# CC2530.net
KiCad netlist of a schematic drawn in Altium Designer
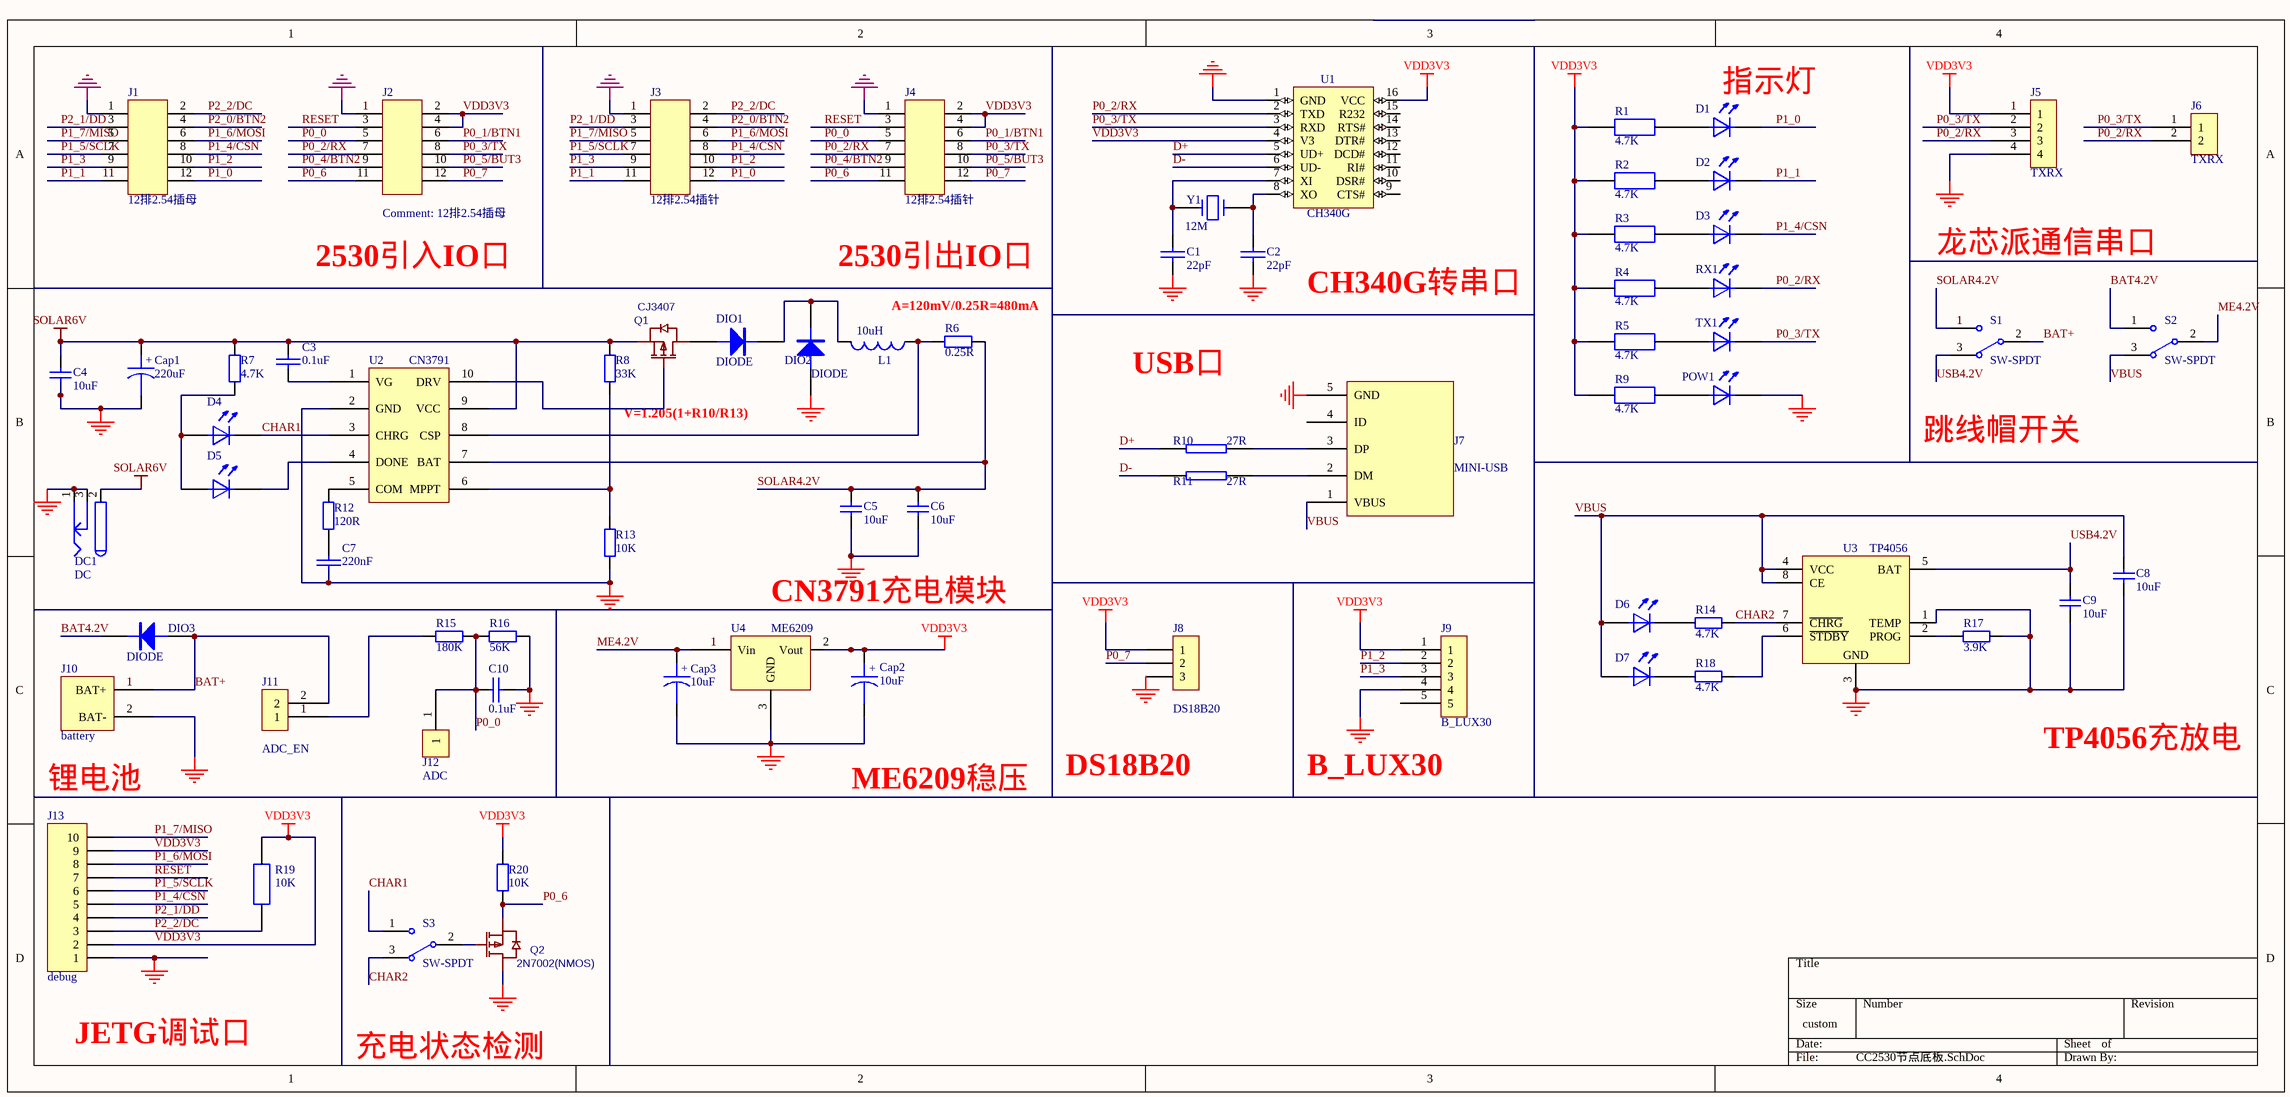
[diagram p0: CC2530节点底板.SchDoc]

(export (version "E")
  (design (tool "Eeschema 10.0.6"))
  (components
    (comp (ref "C1")
      (value "22pF")
      (footprint "C 0603_L")
      (description "Capacitor")
      (libsource (lib "*") (part "CAP"))
    )
    (comp (ref "C2")
      (value "22pF")
      (footprint "C 0603_L")
      (description "Capacitor")
      (libsource (lib "*") (part "CAP"))
    )
    (comp (ref "C3")
      (value "0.1uF")
      (footprint "C 0603_L")
      (description "Capacitor")
      (libsource (lib "*") (part "CAP"))
    )
    (comp (ref "C4")
      (value "10uF")
      (footprint "C 0805_L")
      (description "无极性电容")
      (fields (field (name "PUBLISHER") "Altium Limited"))
      (libsource (lib "Fszhang") (part "Cap"))
    )
    (comp (ref "C5")
      (value "10uF")
      (footprint "C 0805_L")
      (description "无极性电容")
      (fields (field (name "PUBLISHER") "Altium Limited"))
      (libsource (lib "Fszhang") (part "Cap"))
    )
    (comp (ref "C6")
      (value "10uF")
      (footprint "C 0805_L")
      (description "无极性电容")
      (fields (field (name "PUBLISHER") "Altium Limited"))
      (libsource (lib "Fszhang") (part "Cap"))
    )
    (comp (ref "C7")
      (value "220nF")
      (footprint "C 0603_L")
      (description "Capacitor")
      (libsource (lib "*") (part "CAP"))
    )
    (comp (ref "C8")
      (value "10uF")
      (footprint "C 0805_L")
      (description "无极性电容")
      (fields (field (name "PUBLISHER") "Altium Limited"))
      (libsource (lib "Fszhang") (part "Cap"))
    )
    (comp (ref "C9")
      (value "10uF")
      (footprint "C 0805_L")
      (description "无极性电容")
      (fields (field (name "PUBLISHER") "Altium Limited"))
      (libsource (lib "Fszhang") (part "Cap"))
    )
    (comp (ref "C10")
      (value "0.1uF")
      (footprint "C 0603_L")
      (description "Capacitor")
      (libsource (lib "*") (part "CAP"))
    )
    (comp (ref "Cap1")
      (value "220uF")
      (footprint "CM E(8*10.2)")
      (description "Capacitor")
      (libsource (lib "*") (part "CAPACITOR POL"))
    )
    (comp (ref "Cap2")
      (value "10uF")
      (footprint "CM C(5*5.4)")
      (description "Capacitor")
      (libsource (lib "*") (part "CAPACITOR POL"))
    )
    (comp (ref "Cap3")
      (value "10uF")
      (footprint "CM C(5*5.4)")
      (description "Capacitor")
      (libsource (lib "*") (part "CAPACITOR POL"))
    )
    (comp (ref "D1") (value "~") (footprint "LED 0805W") (libsource (lib "*") (part "LED")))
    (comp (ref "D2") (value "~") (footprint "LED 0805W") (libsource (lib "*") (part "LED")))
    (comp (ref "D3") (value "~") (footprint "LED 0805W") (libsource (lib "*") (part "LED")))
    (comp (ref "D4") (value "~") (footprint "LED 0805R") (libsource (lib "*") (part "LED")))
    (comp (ref "D5") (value "~") (footprint "LED 0805G") (libsource (lib "*") (part "LED")))
    (comp (ref "D6") (value "~") (footprint "LED 0805R") (libsource (lib "*") (part "LED")))
    (comp (ref "D7") (value "~") (footprint "LED 0805G") (libsource (lib "*") (part "LED")))
    (comp (ref "DC1")
      (value "DC")
      (footprint "DC-005")
      (description "Low Voltage Power Supply Connector")
      (fields (field (name "PUBLISHER") "*"))
      (libsource (lib "*") (part "PWR2.5"))
    )
    (comp (ref "DIO1")
      (value "DIODE")
      (footprint "SOD-323")
      (description "1N5817")
      (libsource (lib "*") (part "DIODE"))
    )
    (comp (ref "DIO2")
      (value "DIODE")
      (footprint "SOD-323")
      (description "1N5817")
      (libsource (lib "*") (part "DIODE"))
    )
    (comp (ref "DIO3")
      (value "DIODE")
      (footprint "SOD-323")
      (description "1N5817")
      (libsource (lib "*") (part "DIODE"))
    )
    (comp (ref "J1") (value "12排2.54插母") (footprint "HDR2.54-M-LS-2x6P") (libsource (lib "*") (part "CON12")))
    (comp (ref "J2") (value "12排2.54插母") (footprint "HDR2.54-M-LS-2x6P") (libsource (lib "*") (part "CON12")))
    (comp (ref "J3") (value "12排2.54插针") (footprint "HDR2.54-LI-2x6P") (libsource (lib "*") (part "CON12")))
    (comp (ref "J4") (value "12排2.54插针") (footprint "HDR2.54-LI-2x6P") (libsource (lib "*") (part "CON12")))
    (comp (ref "J5")
      (value "TXRX")
      (footprint "HDR2.54-M-LI-4P")
      (libsource (lib "串口收发") (part "Component_1"))
    )
    (comp (ref "J6") (value "TXRX") (footprint "HDR2.54-LI-2P") (libsource (lib "") (part "Component_1_1")))
    (comp (ref "J7")
      (value "MINI-USB")
      (footprint "USB-MINI-A")
      (libsource (lib "MINI-USB") (part "Component_1"))
    )
    (comp (ref "J8")
      (value "~")
      (footprint "HDR2.54-M-LI-3P")
      (description "Connector")
      (libsource (lib "*") (part "CON3"))
    )
    (comp (ref "J9")
      (value "B_LUX30")
      (footprint "HDR2.0-M-LI-5P")
      (libsource (lib "B_LUX30") (part "Component_1"))
    )
    (comp (ref "J10") (value "battery") (footprint "单节贴片锂电池座") (libsource (lib "BAT") (part "Component_1")))
    (comp (ref "J11")
      (value "ADC_EN")
      (footprint "HDR2.54-LI-2P")
      (libsource (lib "") (part "Component_1_2"))
    )
    (comp (ref "J12")
      (value "ADC")
      (footprint "HDR2.54-LI-1P")
      (libsource (lib "ADC采样") (part "Component_1"))
    )
    (comp (ref "J13")
      (value "debug")
      (footprint "DC-2.54-L-Z-10P")
      (description "Connector")
      (libsource (lib "*") (part "CON10"))
    )
    (comp (ref "L1")
      (value "10uH")
      (footprint "NR5020")
      (description "NR5020")
      (libsource (lib "*") (part "L"))
    )
    (comp (ref "POW1") (value "~") (footprint "LED 0805R") (libsource (lib "*") (part "LED")))
    (comp (ref "Q1")
      (value "CJ3407")
      (footprint "SOT-23")
      (fields
        (field (name "BOM_MANUFACTURER PART") "AOD413A")
        (field (name "BOM_SUPPLIER PART") "C115837")
        (field (name "CONTRIBUTOR") "LCSC")
      )
      (libsource (lib "altium-import") (part "root_1_AOD413A_"))
    )
    (comp (ref "Q2")
      (value "2N7002(NMOS)")
      (footprint "SOT-23")
      (description "2N7002")
      (fields
        (field (name "BOM_MANUFACTURER PART") "AOD413A")
        (field (name "BOM_SUPPLIER PART") "C115837")
        (field (name "CONTRIBUTOR") "LCSC")
      )
      (libsource (lib "altium-import") (part "root_0_AOD413A_"))
    )
    (comp (ref "R1") (value "4.7K") (footprint "R 0603-HP_L") (libsource (lib "*") (part "R")))
    (comp (ref "R2") (value "4.7K") (footprint "R 0603-HP_L") (libsource (lib "*") (part "R")))
    (comp (ref "R3") (value "4.7K") (footprint "R 0603-HP_L") (libsource (lib "*") (part "R")))
    (comp (ref "R4") (value "4.7K") (footprint "R 0603-HP_L") (libsource (lib "*") (part "R")))
    (comp (ref "R5") (value "4.7K") (footprint "R 0603-HP_L") (libsource (lib "*") (part "R")))
    (comp (ref "R6")
      (value "0.25R")
      (footprint "R 0805-HP_L")
      (description "贴片电阻")
      (fields (field (name "PUBLISHER") "Altium Limited"))
      (libsource (lib "Fszhang") (part "Res1"))
    )
    (comp (ref "R7")
      (value "4.7K")
      (footprint "R 0603-HP_L")
      (description "贴片电阻")
      (fields (field (name "PUBLISHER") "Altium Limited"))
      (libsource (lib "") (part "Res1_1"))
    )
    (comp (ref "R8")
      (value "33K")
      (footprint "R 0603-HP_L")
      (description "贴片电阻")
      (fields (field (name "Comment") "75K") (field (name "PUBLISHER") "Altium Limited"))
      (libsource (lib "") (part "Res1_1"))
    )
    (comp (ref "R9") (value "4.7K") (footprint "R 0603-HP_L") (libsource (lib "*") (part "R")))
    (comp (ref "R10") (value "27R") (footprint "R 0603-HP_L") (libsource (lib "*") (part "RES2")))
    (comp (ref "R11") (value "27R") (footprint "R 0603-HP_L") (libsource (lib "*") (part "RES2")))
    (comp (ref "R12")
      (value "120R")
      (footprint "R 0603-HP_L")
      (description "贴片电阻")
      (fields (field (name "PUBLISHER") "Altium Limited"))
      (libsource (lib "") (part "Res1_1"))
    )
    (comp (ref "R13")
      (value "10K")
      (footprint "R 0603-HP_L")
      (description "贴片电阻")
      (fields (field (name "PUBLISHER") "Altium Limited"))
      (libsource (lib "") (part "Res1_1"))
    )
    (comp (ref "R14")
      (value "4.7K")
      (footprint "R 0603-HP_L")
      (description "贴片电阻")
      (fields (field (name "Comment") "1K") (field (name "PUBLISHER") "Altium Limited"))
      (libsource (lib "Fszhang") (part "Res1"))
    )
    (comp (ref "R15")
      (value "180K")
      (footprint "R 0603-HP_L")
      (description "贴片电阻")
      (fields (field (name "Comment") "168K") (field (name "PUBLISHER") "Altium Limited"))
      (libsource (lib "Fszhang") (part "Res1"))
    )
    (comp (ref "R16")
      (value "56K")
      (footprint "R 0603-HP_L")
      (description "贴片电阻")
      (fields (field (name "PUBLISHER") "Altium Limited"))
      (libsource (lib "Fszhang") (part "Res1"))
    )
    (comp (ref "R17")
      (value "3.9K")
      (footprint "R 0603-HP_L")
      (description "贴片电阻")
      (fields (field (name "PUBLISHER") "Altium Limited"))
      (libsource (lib "Fszhang") (part "Res1"))
    )
    (comp (ref "R18")
      (value "4.7K")
      (footprint "R 0603-HP_L")
      (description "贴片电阻")
      (fields (field (name "Comment") "1K") (field (name "PUBLISHER") "Altium Limited"))
      (libsource (lib "Fszhang") (part "Res1"))
    )
    (comp (ref "R19") (value "10K") (footprint "R 0603-HP_L") (libsource (lib "*") (part "R")))
    (comp (ref "R20")
      (value "10K")
      (footprint "R 0603-HP_L")
      (description "贴片电阻")
      (fields (field (name "Comment") "168K") (field (name "PUBLISHER") "Altium Limited"))
      (libsource (lib "") (part "Res1_1"))
    )
    (comp (ref "RX1") (value "~") (footprint "LED 0805R") (libsource (lib "*") (part "LED")))
    (comp (ref "S1")
      (value "SW-SPDT")
      (footprint "HDR2.54-LI-3P")
      (description "开关")
      (fields (field (name "PUBLISHER") "Altium Limited"))
      (libsource (lib "Fszhang") (part "SW-SPDT"))
    )
    (comp (ref "S2")
      (value "SW-SPDT")
      (footprint "HDR2.54-LI-3P")
      (description "开关")
      (fields (field (name "PUBLISHER") "Altium Limited"))
      (libsource (lib "Fszhang") (part "SW-SPDT"))
    )
    (comp (ref "S3")
      (value "SW-SPDT")
      (footprint "HDR2.54-LI-3P")
      (description "开关")
      (fields (field (name "PUBLISHER") "Altium Limited"))
      (libsource (lib "Fszhang") (part "SW-SPDT"))
    )
    (comp (ref "TX1") (value "~") (footprint "LED 0805R") (libsource (lib "*") (part "LED")))
    (comp (ref "U1")
      (value "CH340G")
      (footprint "SOP16")
      (description "CH340")
      (libsource (lib "*") (part "CH340G"))
    )
    (comp (ref "U2")
      (value "CN3791")
      (footprint "SSOP-10_150mil")
      (libsource (lib "CN3791") (part "Component_1"))
    )
    (comp (ref "U3")
      (value "TP4056")
      (footprint "SOP8")
      (description "锂电池充电管理")
      (libsource (lib "Fszhang") (part "TP4056"))
    )
    (comp (ref "U4") (value "ME6209") (footprint "SOT89_M") (libsource (lib "ME6209") (part "Component_1")))
    (comp (ref "Y1")
      (value "12M")
      (footprint "OSC HC-49S")
      (description "32K")
      (libsource (lib "*") (part "CRYSTAL"))
    )
  )
  (nets
    (net (code "1") (name "/BAT+") (class "Default")
      (node (ref "DIO3") (pin "1") (pinfunction "A_1") (pintype "passive"))
      (node (ref "J10") (pin "1") (pinfunction "BAT+_1") (pintype "passive"))
      (node (ref "J11") (pin "2") (pinfunction "2_2") (pintype "passive"))
      (node (ref "S1") (pin "2") (pinfunction "2_2") (pintype "passive"))
    )
    (net (code "2") (name "/BAT4.2V") (class "Default")
      (node (ref "DIO3") (pin "2") (pinfunction "K_2") (pintype "passive"))
      (node (ref "S2") (pin "1") (pinfunction "1_1") (pintype "passive"))
    )
    (net (code "3") (name "/CHAR1") (class "Default")
      (node (ref "D4") (pin "2") (pinfunction "2_2") (pintype "passive"))
      (node (ref "S3") (pin "1") (pinfunction "1_1") (pintype "passive"))
      (node (ref "U2") (pin "3") (pinfunction "CHRG_3") (pintype "passive"))
    )
    (net (code "4") (name "/CHAR2") (class "Default")
      (node (ref "R14") (pin "1") (pinfunction "1_1") (pintype "passive"))
      (node (ref "S3") (pin "3") (pinfunction "3_3") (pintype "passive"))
      (node (ref "U3") (pin "7") (pinfunction "~{CHRG}_7") (pintype "passive"))
    )
    (net (code "5") (name "/D+") (class "Default")
      (node (ref "R10") (pin "1") (pinfunction "1_1") (pintype "passive"))
      (node (ref "U1") (pin "5") (pinfunction "UD+_5") (pintype "bidirectional"))
    )
    (net (code "6") (name "/D-") (class "Default")
      (node (ref "R11") (pin "1") (pinfunction "1_1") (pintype "passive"))
      (node (ref "U1") (pin "6") (pinfunction "UD-_6") (pintype "bidirectional"))
    )
    (net (code "7") (name "/ME4.2V") (class "Default")
      (node (ref "Cap3") (pin "1") (pinfunction "1_1") (pintype "passive"))
      (node (ref "S2") (pin "2") (pinfunction "2_2") (pintype "passive"))
      (node (ref "U4") (pin "1") (pinfunction "Vin_1") (pintype "passive"))
    )
    (net (code "8") (name "/P0_0") (class "Default")
      (node (ref "C10") (pin "2") (pinfunction "2_2") (pintype "passive"))
      (node (ref "J12") (pin "1") (pinfunction "1_1") (pintype "passive"))
      (node (ref "J2") (pin "5") (pinfunction "5_5") (pintype "passive"))
      (node (ref "J4") (pin "5") (pinfunction "5_5") (pintype "passive"))
      (node (ref "R15") (pin "1") (pinfunction "1_1") (pintype "passive"))
      (node (ref "R16") (pin "2") (pinfunction "2_2") (pintype "passive"))
    )
    (net (code "9") (name "/P0_1{slash}BTN1") (class "Default")
      (node (ref "J2") (pin "6") (pinfunction "6_6") (pintype "passive"))
      (node (ref "J4") (pin "6") (pinfunction "6_6") (pintype "passive"))
    )
    (net (code "10") (name "/P0_2{slash}RX") (class "Default")
      (node (ref "J2") (pin "7") (pinfunction "7_7") (pintype "passive"))
      (node (ref "J4") (pin "7") (pinfunction "7_7") (pintype "passive"))
      (node (ref "J5") (pin "3") (pinfunction "3_3") (pintype "passive"))
      (node (ref "J6") (pin "2") (pinfunction "2_2") (pintype "passive"))
      (node (ref "RX1") (pin "2") (pinfunction "2_2") (pintype "passive"))
      (node (ref "U1") (pin "2") (pinfunction "TXD_2") (pintype "bidirectional"))
    )
    (net (code "11") (name "/P0_3{slash}TX") (class "Default")
      (node (ref "J2") (pin "8") (pinfunction "8_8") (pintype "passive"))
      (node (ref "J4") (pin "8") (pinfunction "8_8") (pintype "passive"))
      (node (ref "J5") (pin "2") (pinfunction "2_2") (pintype "passive"))
      (node (ref "J6") (pin "1") (pinfunction "1_1") (pintype "passive"))
      (node (ref "TX1") (pin "2") (pinfunction "2_2") (pintype "passive"))
      (node (ref "U1") (pin "3") (pinfunction "RXD_3") (pintype "bidirectional"))
    )
    (net (code "12") (name "/P0_4{slash}BTN2") (class "Default")
      (node (ref "J2") (pin "9") (pinfunction "9_9") (pintype "passive"))
      (node (ref "J4") (pin "9") (pinfunction "9_9") (pintype "passive"))
    )
    (net (code "13") (name "/P0_5{slash}BUT3") (class "Default")
      (node (ref "J2") (pin "10") (pinfunction "10_10") (pintype "passive"))
      (node (ref "J4") (pin "10") (pinfunction "10_10") (pintype "passive"))
    )
    (net (code "14") (name "/P0_6") (class "Default")
      (node (ref "J2") (pin "11") (pinfunction "11_11") (pintype "passive"))
      (node (ref "J4") (pin "11") (pinfunction "11_11") (pintype "passive"))
      (node (ref "Q2") (pin "3") (pinfunction "S_3") (pintype "passive"))
      (node (ref "R20") (pin "2") (pinfunction "2_2") (pintype "passive"))
    )
    (net (code "15") (name "/P0_7") (class "Default")
      (node (ref "J2") (pin "12") (pinfunction "12_12") (pintype "passive"))
      (node (ref "J4") (pin "12") (pinfunction "12_12") (pintype "passive"))
      (node (ref "J8") (pin "2") (pinfunction "2_2") (pintype "passive"))
    )
    (net (code "16") (name "/P1_0") (class "Default")
      (node (ref "D1") (pin "2") (pinfunction "2_2") (pintype "passive"))
      (node (ref "J1") (pin "12") (pinfunction "12_12") (pintype "passive"))
      (node (ref "J3") (pin "12") (pinfunction "12_12") (pintype "passive"))
    )
    (net (code "17") (name "/P1_1") (class "Default")
      (node (ref "D2") (pin "2") (pinfunction "2_2") (pintype "passive"))
      (node (ref "J1") (pin "11") (pinfunction "11_11") (pintype "passive"))
      (node (ref "J3") (pin "11") (pinfunction "11_11") (pintype "passive"))
    )
    (net (code "18") (name "/P1_2") (class "Default")
      (node (ref "J1") (pin "10") (pinfunction "10_10") (pintype "passive"))
      (node (ref "J3") (pin "10") (pinfunction "10_10") (pintype "passive"))
      (node (ref "J9") (pin "2") (pinfunction "2_2") (pintype "passive"))
    )
    (net (code "19") (name "/P1_3") (class "Default")
      (node (ref "J1") (pin "9") (pinfunction "9_9") (pintype "passive"))
      (node (ref "J3") (pin "9") (pinfunction "9_9") (pintype "passive"))
      (node (ref "J9") (pin "3") (pinfunction "3_3") (pintype "passive"))
    )
    (net (code "20") (name "/P1_4{slash}CSN") (class "Default")
      (node (ref "D3") (pin "2") (pinfunction "2_2") (pintype "passive"))
      (node (ref "J1") (pin "8") (pinfunction "8_8") (pintype "passive"))
      (node (ref "J13") (pin "5") (pinfunction "5_5") (pintype "passive"))
      (node (ref "J3") (pin "8") (pinfunction "8_8") (pintype "passive"))
    )
    (net (code "21") (name "/P1_5{slash}SCLK") (class "Default")
      (node (ref "J1") (pin "7") (pinfunction "7_7") (pintype "passive"))
      (node (ref "J13") (pin "6") (pinfunction "6_6") (pintype "passive"))
      (node (ref "J3") (pin "7") (pinfunction "7_7") (pintype "passive"))
    )
    (net (code "22") (name "/P1_6{slash}MOSI") (class "Default")
      (node (ref "J1") (pin "6") (pinfunction "6_6") (pintype "passive"))
      (node (ref "J13") (pin "8") (pinfunction "8_8") (pintype "passive"))
      (node (ref "J3") (pin "6") (pinfunction "6_6") (pintype "passive"))
    )
    (net (code "23") (name "/P1_7{slash}MISO") (class "Default")
      (node (ref "J1") (pin "5") (pinfunction "5_5") (pintype "passive"))
      (node (ref "J13") (pin "10") (pinfunction "10_10") (pintype "passive"))
      (node (ref "J3") (pin "5") (pinfunction "5_5") (pintype "passive"))
    )
    (net (code "24") (name "/P2_0{slash}BTN2") (class "Default")
      (node (ref "J1") (pin "4") (pinfunction "4_4") (pintype "passive"))
      (node (ref "J3") (pin "4") (pinfunction "4_4") (pintype "passive"))
    )
    (net (code "25") (name "/P2_1{slash}DD") (class "Default")
      (node (ref "J1") (pin "3") (pinfunction "3_3") (pintype "passive"))
      (node (ref "J13") (pin "4") (pinfunction "4_4") (pintype "passive"))
      (node (ref "J3") (pin "3") (pinfunction "3_3") (pintype "passive"))
    )
    (net (code "26") (name "/P2_2{slash}DC") (class "Default")
      (node (ref "J1") (pin "2") (pinfunction "2_2") (pintype "passive"))
      (node (ref "J13") (pin "3") (pinfunction "3_3") (pintype "passive"))
      (node (ref "J3") (pin "2") (pinfunction "2_2") (pintype "passive"))
      (node (ref "R19") (pin "1") (pinfunction "1_1") (pintype "passive"))
    )
    (net (code "27") (name "/RESET") (class "Default")
      (node (ref "J13") (pin "7") (pinfunction "7_7") (pintype "passive"))
      (node (ref "J2") (pin "3") (pinfunction "3_3") (pintype "passive"))
      (node (ref "J4") (pin "3") (pinfunction "3_3") (pintype "passive"))
    )
    (net (code "28") (name "/SOLAR4.2V") (class "Default")
      (node (ref "C5") (pin "1") (pinfunction "1_1") (pintype "passive"))
      (node (ref "C6") (pin "1") (pinfunction "1_1") (pintype "passive"))
      (node (ref "R6") (pin "1") (pinfunction "1_1") (pintype "passive"))
      (node (ref "S1") (pin "1") (pinfunction "1_1") (pintype "passive"))
      (node (ref "U2") (pin "7") (pinfunction "BAT_7") (pintype "passive"))
    )
    (net (code "29") (name "/USB4.2V") (class "Default")
      (node (ref "C9") (pin "1") (pinfunction "1_1") (pintype "passive"))
      (node (ref "S1") (pin "3") (pinfunction "3_3") (pintype "passive"))
      (node (ref "U3") (pin "5") (pinfunction "BAT_5") (pintype "passive"))
    )
    (net (code "30") (name "/VBUS") (class "Default")
      (node (ref "C8") (pin "2") (pinfunction "2_2") (pintype "passive"))
      (node (ref "D6") (pin "1") (pinfunction "1_1") (pintype "passive"))
      (node (ref "D7") (pin "1") (pinfunction "1_1") (pintype "passive"))
      (node (ref "J7") (pin "1") (pinfunction "VBUS_1") (pintype "power_in"))
      (node (ref "S2") (pin "3") (pinfunction "3_3") (pintype "passive"))
      (node (ref "U3") (pin "4") (pinfunction "VCC_4") (pintype "passive"))
      (node (ref "U3") (pin "8") (pinfunction "CE_8") (pintype "passive"))
    )
    (net (code "31") (name "GND") (class "Default")
      (node (ref "C1") (pin "2") (pinfunction "2_2") (pintype "passive"))
      (node (ref "C10") (pin "1") (pinfunction "1_1") (pintype "passive"))
      (node (ref "C2") (pin "2") (pinfunction "2_2") (pintype "passive"))
      (node (ref "C4") (pin "2") (pinfunction "2_2") (pintype "passive"))
      (node (ref "C5") (pin "2") (pinfunction "2_2") (pintype "passive"))
      (node (ref "C6") (pin "2") (pinfunction "2_2") (pintype "passive"))
      (node (ref "C7") (pin "2") (pinfunction "2_2") (pintype "passive"))
      (node (ref "C8") (pin "1") (pinfunction "1_1") (pintype "passive"))
      (node (ref "C9") (pin "2") (pinfunction "2_2") (pintype "passive"))
      (node (ref "Cap1") (pin "2") (pinfunction "2_2") (pintype "passive"))
      (node (ref "Cap2") (pin "2") (pinfunction "2_2") (pintype "passive"))
      (node (ref "Cap3") (pin "2") (pinfunction "2_2") (pintype "passive"))
      (node (ref "DC1") (pin "1") (pinfunction "1_1") (pintype "power_in"))
      (node (ref "DC1") (pin "3") (pinfunction "3_3") (pintype "power_in"))
      (node (ref "DIO2") (pin "1") (pinfunction "A_1") (pintype "passive"))
      (node (ref "J1") (pin "1") (pinfunction "1_1") (pintype "passive"))
      (node (ref "J10") (pin "2") (pinfunction "BAT-_2") (pintype "passive"))
      (node (ref "J13") (pin "1") (pinfunction "1_1") (pintype "passive"))
      (node (ref "J2") (pin "1") (pinfunction "1_1") (pintype "passive"))
      (node (ref "J3") (pin "1") (pinfunction "1_1") (pintype "passive"))
      (node (ref "J4") (pin "1") (pinfunction "1_1") (pintype "passive"))
      (node (ref "J5") (pin "4") (pinfunction "4_4") (pintype "passive"))
      (node (ref "J7") (pin "5") (pinfunction "GND_5") (pintype "power_in"))
      (node (ref "J8") (pin "3") (pinfunction "3_3") (pintype "passive"))
      (node (ref "J9") (pin "4") (pinfunction "4_4") (pintype "passive"))
      (node (ref "POW1") (pin "2") (pinfunction "2_2") (pintype "passive"))
      (node (ref "Q2") (pin "2") (pinfunction "D_2") (pintype "passive"))
      (node (ref "R13") (pin "2") (pinfunction "2_2") (pintype "passive"))
      (node (ref "R16") (pin "1") (pinfunction "1_1") (pintype "passive"))
      (node (ref "R17") (pin "1") (pinfunction "1_1") (pintype "passive"))
      (node (ref "U1") (pin "1") (pinfunction "GND_1") (pintype "bidirectional"))
      (node (ref "U2") (pin "2") (pinfunction "GND_2") (pintype "passive"))
      (node (ref "U3") (pin "1") (pinfunction "TEMP_1") (pintype "passive"))
      (node (ref "U3") (pin "3") (pinfunction "GND_3") (pintype "passive"))
      (node (ref "U4") (pin "3") (pinfunction "GND_3") (pintype "passive"))
    )
    (net (code "32") (name "Net-(C7-Pad1)") (class "Default")
      (node (ref "C7") (pin "1") (pinfunction "1_1") (pintype "passive"))
      (node (ref "R12") (pin "2") (pinfunction "2_2") (pintype "passive"))
    )
    (net (code "33") (name "Net-(D1-Pad1)") (class "Default")
      (node (ref "D1") (pin "1") (pinfunction "1_1") (pintype "passive"))
      (node (ref "R1") (pin "2") (pinfunction "2_2") (pintype "passive"))
    )
    (net (code "34") (name "Net-(D2-Pad1)") (class "Default")
      (node (ref "D2") (pin "1") (pinfunction "1_1") (pintype "passive"))
      (node (ref "R2") (pin "2") (pinfunction "2_2") (pintype "passive"))
    )
    (net (code "35") (name "Net-(D3-Pad1)") (class "Default")
      (node (ref "D3") (pin "1") (pinfunction "1_1") (pintype "passive"))
      (node (ref "R3") (pin "2") (pinfunction "2_2") (pintype "passive"))
    )
    (net (code "36") (name "Net-(D4-Pad1)") (class "Default")
      (node (ref "D4") (pin "1") (pinfunction "1_1") (pintype "passive"))
      (node (ref "D5") (pin "1") (pinfunction "1_1") (pintype "passive"))
      (node (ref "R7") (pin "2") (pinfunction "2_2") (pintype "passive"))
    )
    (net (code "37") (name "Net-(D6-Pad2)") (class "Default")
      (node (ref "D6") (pin "2") (pinfunction "2_2") (pintype "passive"))
      (node (ref "R14") (pin "2") (pinfunction "2_2") (pintype "passive"))
    )
    (net (code "38") (name "Net-(D7-Pad2)") (class "Default")
      (node (ref "D7") (pin "2") (pinfunction "2_2") (pintype "passive"))
      (node (ref "R18") (pin "2") (pinfunction "2_2") (pintype "passive"))
    )
    (net (code "39") (name "Net-(DIO1-A)") (class "Default")
      (node (ref "DIO1") (pin "1") (pinfunction "A_1") (pintype "passive"))
      (node (ref "Q1") (pin "2") (pinfunction "D_2") (pintype "passive"))
    )
    (net (code "40") (name "Net-(DIO1-K)") (class "Default")
      (node (ref "DIO1") (pin "2") (pinfunction "K_2") (pintype "passive"))
      (node (ref "DIO2") (pin "2") (pinfunction "K_2") (pintype "passive"))
      (node (ref "L1") (pin "1") (pinfunction "1_1") (pintype "passive"))
    )
    (net (code "41") (name "Net-(J7-DM)") (class "Default")
      (node (ref "J7") (pin "2") (pinfunction "DM_2") (pintype "passive"))
      (node (ref "R11") (pin "2") (pinfunction "2_2") (pintype "passive"))
    )
    (net (code "42") (name "Net-(J7-DP)") (class "Default")
      (node (ref "J7") (pin "3") (pinfunction "DP_3") (pintype "passive"))
      (node (ref "R10") (pin "2") (pinfunction "2_2") (pintype "passive"))
    )
    (net (code "43") (name "Net-(J11-Pad1)") (class "Default")
      (node (ref "J11") (pin "1") (pinfunction "1_1") (pintype "passive"))
      (node (ref "R15") (pin "2") (pinfunction "2_2") (pintype "passive"))
    )
    (net (code "44") (name "Net-(POW1-Pad1)") (class "Default")
      (node (ref "POW1") (pin "1") (pinfunction "1_1") (pintype "passive"))
      (node (ref "R9") (pin "2") (pinfunction "2_2") (pintype "passive"))
    )
    (net (code "45") (name "Net-(Q1-G)") (class "Default")
      (node (ref "Q1") (pin "1") (pinfunction "G_1") (pintype "passive"))
      (node (ref "U2") (pin "10") (pinfunction "DRV_10") (pintype "passive"))
    )
    (net (code "46") (name "Net-(Q2-G)") (class "Default")
      (node (ref "Q2") (pin "1") (pinfunction "G_1") (pintype "passive"))
      (node (ref "S3") (pin "2") (pinfunction "2_2") (pintype "passive"))
    )
    (net (code "47") (name "Net-(R4-Pad2)") (class "Default")
      (node (ref "R4") (pin "2") (pinfunction "2_2") (pintype "passive"))
      (node (ref "RX1") (pin "1") (pinfunction "1_1") (pintype "passive"))
    )
    (net (code "48") (name "Net-(R5-Pad2)") (class "Default")
      (node (ref "R5") (pin "2") (pinfunction "2_2") (pintype "passive"))
      (node (ref "TX1") (pin "1") (pinfunction "1_1") (pintype "passive"))
    )
    (net (code "49") (name "Net-(U1-XI)") (class "Default")
      (node (ref "C1") (pin "1") (pinfunction "1_1") (pintype "passive"))
      (node (ref "U1") (pin "7") (pinfunction "XI_7") (pintype "bidirectional"))
      (node (ref "Y1") (pin "1") (pinfunction "1_1") (pintype "passive"))
    )
    (net (code "50") (name "Net-(U1-XO)") (class "Default")
      (node (ref "C2") (pin "1") (pinfunction "1_1") (pintype "passive"))
      (node (ref "U1") (pin "8") (pinfunction "XO_8") (pintype "bidirectional"))
      (node (ref "Y1") (pin "2") (pinfunction "2_2") (pintype "passive"))
    )
    (net (code "51") (name "Net-(U2-COM)") (class "Default")
      (node (ref "R12") (pin "1") (pinfunction "1_1") (pintype "passive"))
      (node (ref "U2") (pin "5") (pinfunction "COM_5") (pintype "passive"))
    )
    (net (code "52") (name "Net-(U2-CSP)") (class "Default")
      (node (ref "L1") (pin "2") (pinfunction "2_2") (pintype "passive"))
      (node (ref "R6") (pin "2") (pinfunction "2_2") (pintype "passive"))
      (node (ref "U2") (pin "8") (pinfunction "CSP_8") (pintype "passive"))
    )
    (net (code "53") (name "Net-(U2-DONE)") (class "Default")
      (node (ref "D5") (pin "2") (pinfunction "2_2") (pintype "passive"))
      (node (ref "U2") (pin "4") (pinfunction "DONE_4") (pintype "passive"))
    )
    (net (code "54") (name "Net-(U2-MPPT)") (class "Default")
      (node (ref "R13") (pin "1") (pinfunction "1_1") (pintype "passive"))
      (node (ref "R8") (pin "2") (pinfunction "2_2") (pintype "passive"))
      (node (ref "U2") (pin "6") (pinfunction "MPPT_6") (pintype "passive"))
    )
    (net (code "55") (name "Net-(U2-VG)") (class "Default")
      (node (ref "C3") (pin "2") (pinfunction "2_2") (pintype "passive"))
      (node (ref "U2") (pin "1") (pinfunction "VG_1") (pintype "passive"))
    )
    (net (code "56") (name "Net-(U3-PROG)") (class "Default")
      (node (ref "R17") (pin "2") (pinfunction "2_2") (pintype "passive"))
      (node (ref "U3") (pin "2") (pinfunction "PROG_2") (pintype "passive"))
    )
    (net (code "57") (name "Net-(U3-~{STDBY})") (class "Default")
      (node (ref "R18") (pin "1") (pinfunction "1_1") (pintype "passive"))
      (node (ref "U3") (pin "6") (pinfunction "~{STDBY}_6") (pintype "passive"))
    )
    (net (code "58") (name "SOLAR6V") (class "Default")
      (node (ref "C3") (pin "1") (pinfunction "1_1") (pintype "passive"))
      (node (ref "C4") (pin "1") (pinfunction "1_1") (pintype "passive"))
      (node (ref "Cap1") (pin "1") (pinfunction "1_1") (pintype "passive"))
      (node (ref "DC1") (pin "2") (pinfunction "2_2") (pintype "power_in"))
      (node (ref "Q1") (pin "3") (pinfunction "S_3") (pintype "passive"))
      (node (ref "R7") (pin "1") (pinfunction "1_1") (pintype "passive"))
      (node (ref "R8") (pin "1") (pinfunction "1_1") (pintype "passive"))
      (node (ref "U2") (pin "9") (pinfunction "VCC_9") (pintype "passive"))
    )
    (net (code "59") (name "VDD3V3") (class "Default")
      (node (ref "Cap2") (pin "1") (pinfunction "1_1") (pintype "passive"))
      (node (ref "J13") (pin "2") (pinfunction "2_2") (pintype "passive"))
      (node (ref "J13") (pin "9") (pinfunction "9_9") (pintype "passive"))
      (node (ref "J2") (pin "2") (pinfunction "2_2") (pintype "passive"))
      (node (ref "J2") (pin "4") (pinfunction "4_4") (pintype "passive"))
      (node (ref "J4") (pin "2") (pinfunction "2_2") (pintype "passive"))
      (node (ref "J4") (pin "4") (pinfunction "4_4") (pintype "passive"))
      (node (ref "J5") (pin "1") (pinfunction "1_1") (pintype "passive"))
      (node (ref "J8") (pin "1") (pinfunction "1_1") (pintype "passive"))
      (node (ref "J9") (pin "1") (pinfunction "1_1") (pintype "passive"))
      (node (ref "R1") (pin "1") (pinfunction "1_1") (pintype "passive"))
      (node (ref "R19") (pin "2") (pinfunction "2_2") (pintype "passive"))
      (node (ref "R2") (pin "1") (pinfunction "1_1") (pintype "passive"))
      (node (ref "R20") (pin "1") (pinfunction "1_1") (pintype "passive"))
      (node (ref "R3") (pin "1") (pinfunction "1_1") (pintype "passive"))
      (node (ref "R4") (pin "1") (pinfunction "1_1") (pintype "passive"))
      (node (ref "R5") (pin "1") (pinfunction "1_1") (pintype "passive"))
      (node (ref "R9") (pin "1") (pinfunction "1_1") (pintype "passive"))
      (node (ref "U1") (pin "16") (pinfunction "VCC_16") (pintype "bidirectional"))
      (node (ref "U1") (pin "4") (pinfunction "V3_4") (pintype "bidirectional"))
      (node (ref "U4") (pin "2") (pinfunction "Vout_2") (pintype "passive"))
    )
    (net (code "60") (name "unconnected-(J7-ID-Pad4)") (class "Default")
      (node (ref "J7") (pin "4") (pinfunction "ID_4") (pintype "power_in"))
    )
    (net (code "61") (name "unconnected-(J9-Pad5)") (class "Default")
      (node (ref "J9") (pin "5") (pinfunction "5_5") (pintype "passive"))
    )
    (net (code "62") (name "unconnected-(U1-CTS#-Pad9)") (class "Default")
      (node (ref "U1") (pin "9") (pinfunction "CTS#_9") (pintype "bidirectional"))
    )
    (net (code "63") (name "unconnected-(U1-DCD#-Pad12)") (class "Default")
      (node (ref "U1") (pin "12") (pinfunction "DCD#_12") (pintype "bidirectional"))
    )
    (net (code "64") (name "unconnected-(U1-DSR#-Pad10)") (class "Default")
      (node (ref "U1") (pin "10") (pinfunction "DSR#_10") (pintype "bidirectional"))
    )
    (net (code "65") (name "unconnected-(U1-DTR#-Pad13)") (class "Default")
      (node (ref "U1") (pin "13") (pinfunction "DTR#_13") (pintype "bidirectional"))
    )
    (net (code "66") (name "unconnected-(U1-R232-Pad15)") (class "Default")
      (node (ref "U1") (pin "15") (pinfunction "R232_15") (pintype "bidirectional"))
    )
    (net (code "67") (name "unconnected-(U1-RI#-Pad11)") (class "Default")
      (node (ref "U1") (pin "11") (pinfunction "RI#_11") (pintype "bidirectional"))
    )
    (net (code "68") (name "unconnected-(U1-RTS#-Pad14)") (class "Default")
      (node (ref "U1") (pin "14") (pinfunction "RTS#_14") (pintype "bidirectional"))
    )
  )
)
